# Power_Supply.net
KiCad netlist of a schematic drawn in Altium Designer
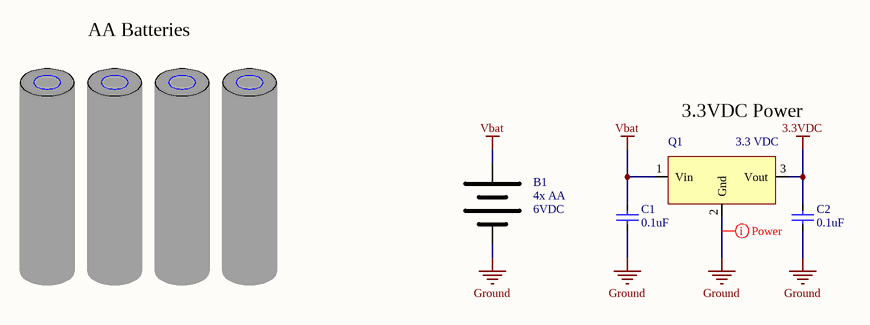
[diagram p0: Power Supply.SchDoc]

(export (version "E")
  (design (tool "Eeschema 10.0.6"))
  (components
    (comp (ref "B1")
      (value "Battery")
      (fields (field (name "QUICKVALUE") "4x AA") (field (name "VOLTAGE") "6VDC"))
      (libsource (lib "Micro") (part "Battery"))
    )
    (comp (ref "B2")
      (value "AA Battery")
      (description "Battery")
      (fields (field (name "VOLTAGE") "1.5VDC"))
      (libsource (lib "Micro") (part "AA Battery"))
    )
    (comp (ref "B3")
      (value "AA Battery")
      (description "Battery")
      (fields (field (name "VOLTAGE") "1.5VDC"))
      (libsource (lib "Micro") (part "AA Battery"))
    )
    (comp (ref "B4")
      (value "AA Battery")
      (description "Battery")
      (fields (field (name "VOLTAGE") "1.5VDC"))
      (libsource (lib "Micro") (part "AA Battery"))
    )
    (comp (ref "B5")
      (value "AA Battery")
      (description "Battery")
      (fields (field (name "VOLTAGE") "1.5VDC"))
      (libsource (lib "Micro") (part "AA Battery"))
    )
    (comp (ref "C1")
      (value "~")
      (footprint "Capacitor - 0603")
      (description "Non-polarized")
      (fields
        (field (name "TOLERANCE") "10%")
        (field (name "VOLTAGE") "50V")
        (field (name "QUICKVALUE") "0.1uF")
      )
      (libsource (lib "EDC Standard Library") (part "Capacitor (Non-polarized)"))
    )
    (comp (ref "C2")
      (value "~")
      (footprint "Capacitor - 0603")
      (description "Non-polarized")
      (fields
        (field (name "TOLERANCE") "10%")
        (field (name "VOLTAGE") "50V")
        (field (name "QUICKVALUE") "0.1uF")
      )
      (libsource (lib "EDC Standard Library") (part "Capacitor (Non-polarized)"))
    )
    (comp (ref "Q1")
      (value "Voltage Regulator, Fixed")
      (footprint "SOT223-B - v2")
      (fields (field (name "QUICKVALUE") "3.3 VDC"))
      (libsource (lib "EDC Standard Library") (part "Voltage Regulator, Fixed"))
    )
  )
  (nets
    (net (code "1") (name "3.3VDC") (class "Default")
      (node (ref "C2") (pin "1") (pinfunction "1_1") (pintype "passive"))
      (node (ref "Q1") (pin "3") (pinfunction "Vout_3") (pintype "passive"))
    )
    (net (code "2") (name "Ground") (class "Default")
      (node (ref "B1") (pin "2") (pinfunction "Negative_2") (pintype "passive"))
      (node (ref "C1") (pin "2") (pinfunction "2_2") (pintype "passive"))
      (node (ref "C2") (pin "2") (pinfunction "2_2") (pintype "passive"))
      (node (ref "Q1") (pin "2") (pinfunction "Gnd_2") (pintype "passive"))
    )
    (net (code "3") (name "Vbat") (class "Default")
      (node (ref "B1") (pin "1") (pinfunction "Positive_1") (pintype "passive"))
      (node (ref "C1") (pin "1") (pinfunction "1_1") (pintype "passive"))
      (node (ref "Q1") (pin "1") (pinfunction "Vin_1") (pintype "passive"))
    )
  )
)
